# WE_Sch.net
KiCad netlist of a schematic drawn in Altium Designer
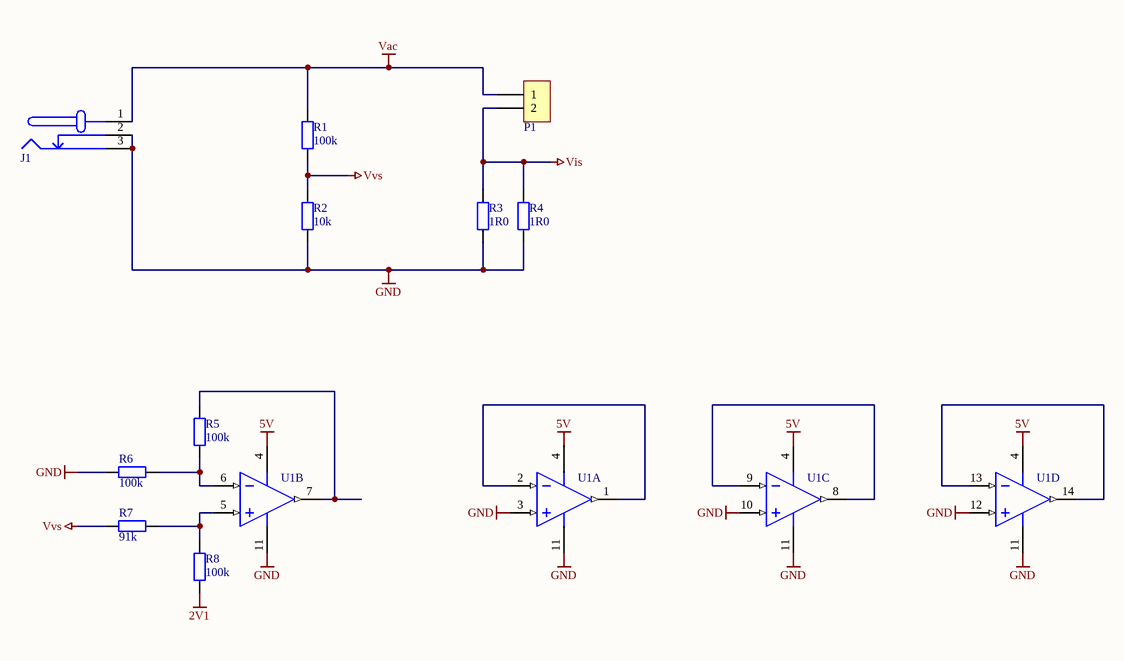
[diagram p0: WE_Sch.SchDoc]

(export (version "E")
  (design (tool "Eeschema 10.0.6"))
  (components
    (comp (ref "J1")
      (value "DC barrel jack")
      (footprint "AC-Socket")
      (description "DC barrel jack connection to AC source")
      (libsource (lib "EE209_Library") (part "AC_Input"))
    )
    (comp (ref "P1")
      (value "Dual Banana Plugs")
      (footprint "Dual Banana Plug")
      (description "Dual banana plugs connection to the AC load")
      (fields (field (name "PUBLISHER") "Altium Limited"))
      (libsource (lib "EE209_Library") (part "AC_Output"))
    )
    (comp (ref "R1")
      (value "100k")
      (footprint "AXIAL-0.4")
      (description "Through hole resistor")
      (fields (field (name "PUBLISHER") "Altium Limited"))
      (libsource (lib "") (part "Res_TH_0AX4_1"))
    )
    (comp (ref "R2")
      (value "10k")
      (footprint "AXIAL-0.4")
      (description "Through hole resistor")
      (fields (field (name "PUBLISHER") "Altium Limited"))
      (libsource (lib "") (part "Res_TH_0AX4_1"))
    )
    (comp (ref "R3")
      (value "1R0")
      (footprint "AXIAL-0.4")
      (description "Through hole resistor")
      (fields (field (name "PUBLISHER") "Altium Limited"))
      (libsource (lib "") (part "Res_TH_0AX4_1"))
    )
    (comp (ref "R4")
      (value "1R0")
      (footprint "AXIAL-0.4")
      (description "Through hole resistor")
      (fields (field (name "PUBLISHER") "Altium Limited"))
      (libsource (lib "") (part "Res_TH_0AX4_1"))
    )
    (comp (ref "R5")
      (value "100k")
      (footprint "AXIAL-0.4")
      (description "Through hole resistor")
      (fields (field (name "PUBLISHER") "Altium Limited"))
      (libsource (lib "") (part "Res_TH_0AX4_2"))
    )
    (comp (ref "R6")
      (value "100k")
      (footprint "AXIAL-0.4")
      (description "Through hole resistor")
      (fields (field (name "PUBLISHER") "Altium Limited"))
      (libsource (lib "EE209_Library") (part "Res_TH_0AX4"))
    )
    (comp (ref "R7")
      (value "91k")
      (footprint "AXIAL-0.4")
      (description "Through hole resistor")
      (fields (field (name "PUBLISHER") "Altium Limited"))
      (libsource (lib "EE209_Library") (part "Res_TH_0AX4"))
    )
    (comp (ref "R8")
      (value "100k")
      (footprint "AXIAL-0.4")
      (description "Through hole resistor")
      (fields (field (name "PUBLISHER") "Altium Limited"))
      (libsource (lib "") (part "Res_TH_0AX4_2"))
    )
    (comp (ref "U1")
      (value "LM324")
      (footprint "DIP-14")
      (description "IC OPAMP GP 14DIP")
      (fields
        (field (name "MANUFACTURER") "ON Semiconductor")
        (field (name "MANUFACTURER PART NUMBER") "LM324N")
      )
      (libsource (lib "EE209_Library") (part "LM324N_TH_DIP16"))
    )
  )
  (nets
    (net (code "1") (name "2V1") (class "Default")
      (node (ref "R8") (pin "1") (pinfunction "1_1") (pintype "passive"))
    )
    (net (code "2") (name "5V") (class "Default")
      (node (ref "U1") (pin "4") (pinfunction "VDD_4") (pintype "power_in"))
    )
    (net (code "3") (name "GND") (class "Default")
      (node (ref "J1") (pin "2") (pinfunction "GND_ALT_2") (pintype "power_in"))
      (node (ref "J1") (pin "3") (pinfunction "GND_3") (pintype "power_in"))
      (node (ref "R2") (pin "2") (pinfunction "2_2") (pintype "passive"))
      (node (ref "R3") (pin "2") (pinfunction "2_2") (pintype "passive"))
      (node (ref "R4") (pin "2") (pinfunction "2_2") (pintype "passive"))
      (node (ref "R6") (pin "1") (pinfunction "1_1") (pintype "passive"))
      (node (ref "U1") (pin "10") (pinfunction "VINC+_10") (pintype "input"))
      (node (ref "U1") (pin "11") (pinfunction "VSS_11") (pintype "power_in"))
      (node (ref "U1") (pin "12") (pinfunction "VIND+_12") (pintype "input"))
      (node (ref "U1") (pin "3") (pinfunction "VINA+_3") (pintype "input"))
    )
    (net (code "4") (name "Net-(U1A-VINA-)") (class "Default")
      (node (ref "U1") (pin "1") (pinfunction "VOUTA_1") (pintype "output"))
      (node (ref "U1") (pin "2") (pinfunction "VINA-_2") (pintype "input"))
    )
    (net (code "5") (name "Net-(U1B-VINB+)") (class "Default")
      (node (ref "R7") (pin "2") (pinfunction "2_2") (pintype "passive"))
      (node (ref "R8") (pin "2") (pinfunction "2_2") (pintype "passive"))
      (node (ref "U1") (pin "5") (pinfunction "VINB+_5") (pintype "input"))
    )
    (net (code "6") (name "Net-(U1B-VINB-)") (class "Default")
      (node (ref "R5") (pin "1") (pinfunction "1_1") (pintype "passive"))
      (node (ref "R6") (pin "2") (pinfunction "2_2") (pintype "passive"))
      (node (ref "U1") (pin "6") (pinfunction "VINB-_6") (pintype "input"))
    )
    (net (code "7") (name "Net-(U1B-VOUTB)") (class "Default")
      (node (ref "R5") (pin "2") (pinfunction "2_2") (pintype "passive"))
      (node (ref "U1") (pin "7") (pinfunction "VOUTB_7") (pintype "output"))
    )
    (net (code "8") (name "Net-(U1C-VINC-)") (class "Default")
      (node (ref "U1") (pin "8") (pinfunction "VOUTC_8") (pintype "output"))
      (node (ref "U1") (pin "9") (pinfunction "VINC-_9") (pintype "input"))
    )
    (net (code "9") (name "Net-(U1D-VIND-)") (class "Default")
      (node (ref "U1") (pin "13") (pinfunction "VIND-_13") (pintype "input"))
      (node (ref "U1") (pin "14") (pinfunction "VOUTD_14") (pintype "output"))
    )
    (net (code "10") (name "Vac") (class "Default")
      (node (ref "J1") (pin "1") (pinfunction "VCC_1") (pintype "power_in"))
      (node (ref "P1") (pin "1") (pinfunction "1_1") (pintype "passive"))
      (node (ref "R1") (pin "1") (pinfunction "1_1") (pintype "passive"))
    )
    (net (code "11") (name "Vis") (class "Default")
      (node (ref "P1") (pin "2") (pinfunction "2_2") (pintype "passive"))
      (node (ref "R3") (pin "1") (pinfunction "1_1") (pintype "passive"))
      (node (ref "R4") (pin "1") (pinfunction "1_1") (pintype "passive"))
    )
    (net (code "12") (name "Vvs") (class "Default")
      (node (ref "R1") (pin "2") (pinfunction "2_2") (pintype "passive"))
      (node (ref "R2") (pin "1") (pinfunction "1_1") (pintype "passive"))
      (node (ref "R7") (pin "1") (pinfunction "1_1") (pintype "passive"))
    )
  )
)
